# Diplomski.net
KiCad netlist of a schematic drawn in EasyEDA
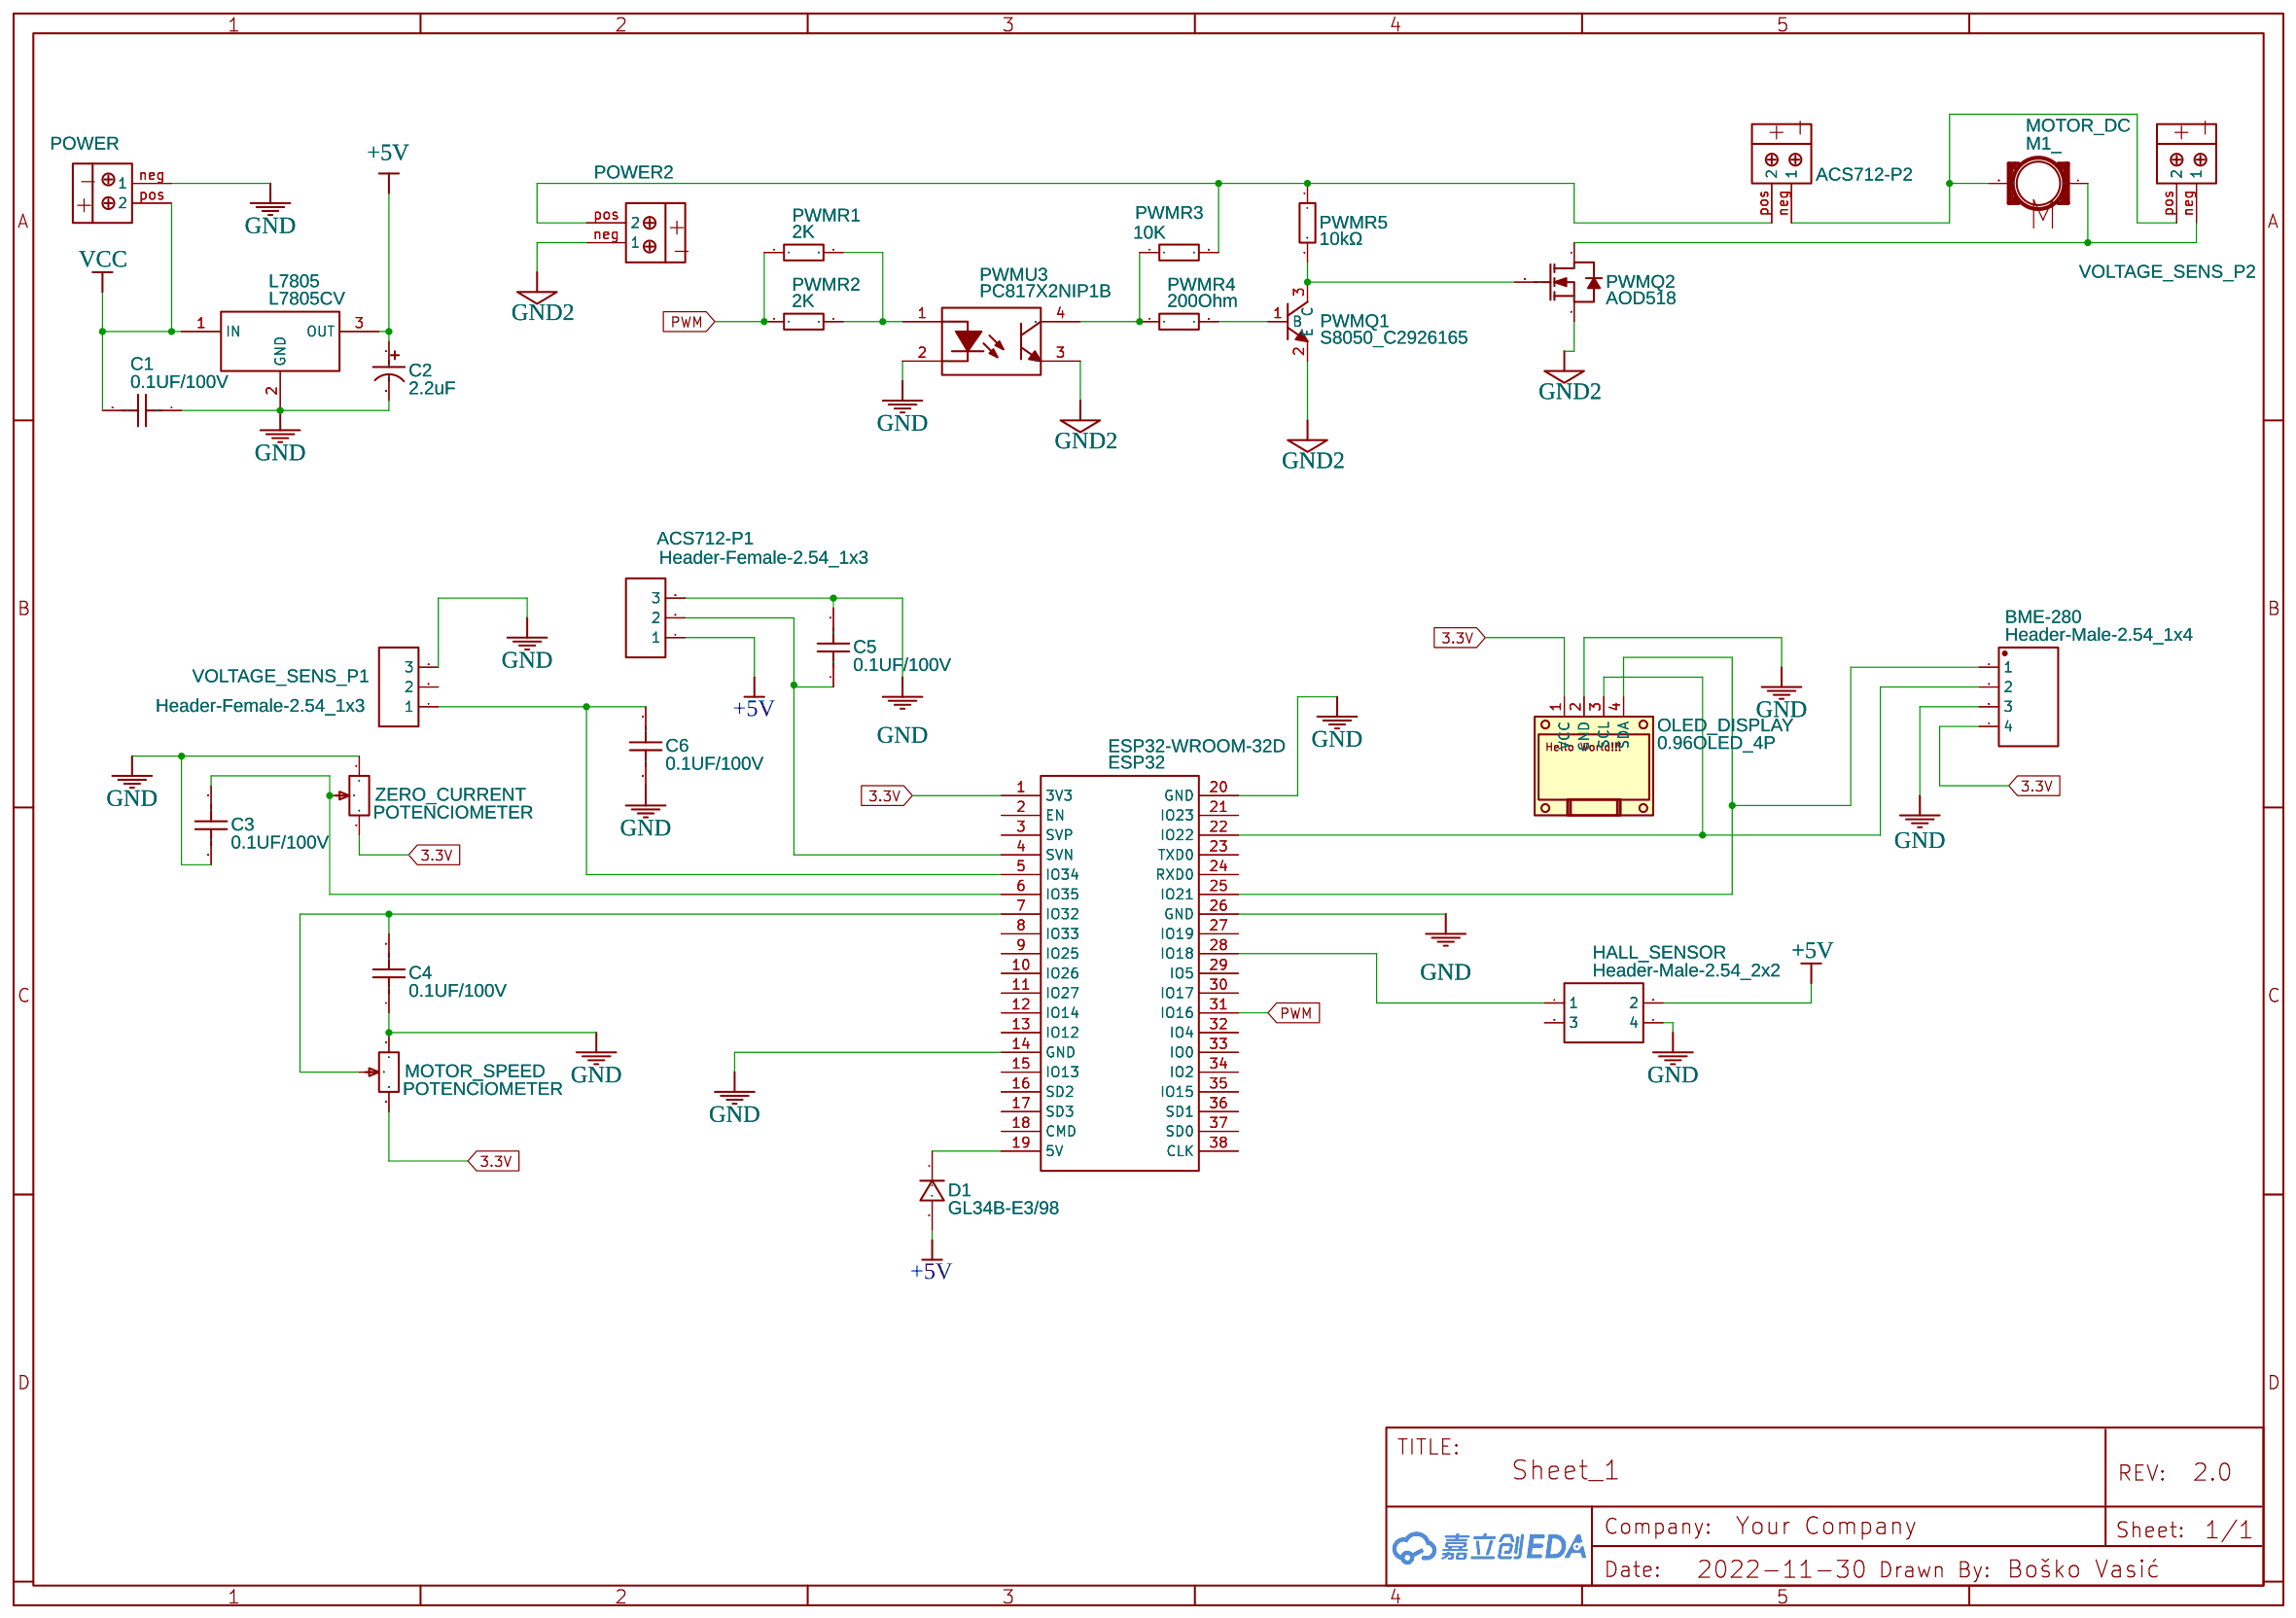
[diagram p0: schematic sheet]

(export (version "E")
  (design (tool "Eeschema 10.0.6"))
  (components
    (comp (ref "ACS712-P1")
      (value "Header-Female-2.54_1x3")
      (fields (field (name "BOM_Supplier Part") "C146243"))
      (libsource (lib "") (part "Header-Female-2.54_1x3_1"))
    )
    (comp (ref "ACS712-P2")
      (value "1X2 POWER PCB CONNECTO COPY")
      (fields (field (name "BOM_Manufacturer Part") "1x2 pin header"))
      (libsource (lib "") (part "1X2 POWER PCB CONNECTO COPY_2"))
    )
    (comp (ref "BME-280")
      (value "Header-Male-2.54_1x4")
      (fields
        (field (name "BOM_Manufacturer Part") "B-2100S04P-A110")
        (field (name "BOM_Supplier Part") "C124378")
      )
      (libsource (lib "") (part "Header-Male-2.54_1x4"))
    )
    (comp (ref "C1")
      (value "0.1UF/100V")
      (fields
        (field (name "BOM_Manufacturer Part") "0.1uF/100V")
        (field (name "BOM_Supplier Part") "C9900010259")
      )
      (libsource (lib "") (part "0.1UF/100V_1"))
    )
    (comp (ref "C2")
      (value "2.2uF")
      (fields
        (field (name "BOM_Manufacturer Part") "ERM1HM2R2D11OT")
        (field (name "BOM_Supplier Part") "C106603")
      )
      (libsource (lib "") (part "2.2UF 50V"))
    )
    (comp (ref "C3")
      (value "0.1UF/100V")
      (fields
        (field (name "BOM_Manufacturer Part") "0.1uF/100V")
        (field (name "BOM_Supplier Part") "C9900010259")
      )
      (libsource (lib "") (part "0.1UF/100V"))
    )
    (comp (ref "C4")
      (value "0.1UF/100V")
      (fields
        (field (name "BOM_Manufacturer Part") "0.1uF/100V")
        (field (name "BOM_Supplier Part") "C9900010259")
      )
      (libsource (lib "") (part "0.1UF/100V"))
    )
    (comp (ref "C5")
      (value "0.1UF/100V")
      (fields
        (field (name "BOM_Manufacturer Part") "0.1uF/100V")
        (field (name "BOM_Supplier Part") "C9900010259")
      )
      (libsource (lib "") (part "0.1UF/100V"))
    )
    (comp (ref "C6")
      (value "0.1UF/100V")
      (fields
        (field (name "BOM_Manufacturer Part") "0.1uF/100V")
        (field (name "BOM_Supplier Part") "C9900010259")
      )
      (libsource (lib "") (part "0.1UF/100V"))
    )
    (comp (ref "D1")
      (value "GL34B-E3/98")
      (fields (field (name "BOM_Supplier Part") "C222497"))
      (libsource (lib "") (part "GL34B-E3/98"))
    )
    (comp (ref "ESP32-WROOM-32D")
      (value "ESP32")
      (fields (field (name "BOM_Manufacturer Part") "ESP32-DEVKITC-32D"))
      (libsource (lib "") (part "Boiler"))
    )
    (comp (ref "HALL_SENSOR")
      (value "Header-Male-2.54_2x2")
      (fields
        (field (name "BOM_Manufacturer Part") "Double Rows2.54mm2*2pHeaders  Pins")
        (field (name "BOM_Supplier Part") "C66690")
      )
      (libsource (lib "") (part "Header-Male-2.54_2x2"))
    )
    (comp (ref "L7805")
      (value "L7805CV")
      (fields (field (name "BOM_Supplier Part") "C111887"))
      (libsource (lib "") (part "L7805CV"))
    )
    (comp (ref "MOTOR_DC") (value "M1_") (libsource (lib "") (part "Motor_DC")))
    (comp (ref "MOTOR_SPEED")
      (value "POTENCIOMETER")
      (fields (field (name "BOM_Manufacturer Part") "APAE_B10K_Potentiometer_Vertical"))
      (libsource (lib "") (part "POTENCIOMETER"))
    )
    (comp (ref "OLED_DISPLAY") (value "0.96OLED_4P") (libsource (lib "") (part "0.96OLED_4P")))
    (comp (ref "POWER")
      (value "1X2 POWER PCB CONNECTO COPY")
      (fields (field (name "BOM_Manufacturer Part") "1x2 pin header"))
      (libsource (lib "") (part "1X2 POWER PCB CONNECTO COPY"))
    )
    (comp (ref "POWER2")
      (value "POWER PCB CONNECTO 2")
      (fields (field (name "BOM_Manufacturer Part") "1x2 pin header"))
      (libsource (lib "") (part "1X2 POWER PCB CONNECTO COPY_3"))
    )
    (comp (ref "PWMQ1")
      (value "S8050_C2926165")
      (fields
        (field (name "BOM_Manufacturer Part") "S8050LT1 J3Y")
        (field (name "BOM_Supplier Part") "C2926165")
      )
      (libsource (lib "") (part "S8050_C2926165"))
    )
    (comp (ref "PWMQ2")
      (value "AOD518")
      (fields (field (name "BOM_Supplier Part") "C878924"))
      (libsource (lib "") (part "AOD518"))
    )
    (comp (ref "PWMR1")
      (value "2K")
      (fields
        (field (name "BOM_Manufacturer Part") "RC1206FR-070RL")
        (field (name "BOM_Supplier Part") "C137394")
      )
      (libsource (lib "") (part "RC1206FR-070RL"))
    )
    (comp (ref "PWMR2")
      (value "2K")
      (fields
        (field (name "BOM_Manufacturer Part") "RC1206FR-070RL")
        (field (name "BOM_Supplier Part") "C137394")
      )
      (libsource (lib "") (part "RC1206FR-070RL"))
    )
    (comp (ref "PWMR3")
      (value "10K")
      (fields
        (field (name "BOM_Manufacturer Part") "AC0805FR-0710KL")
        (field (name "BOM_Supplier Part") "C140868")
      )
      (libsource (lib "") (part "AC0805FR-0710KL"))
    )
    (comp (ref "PWMR4")
      (value "200Ohm")
      (fields
        (field (name "BOM_Manufacturer Part") "AC0805FR-0710KL")
        (field (name "BOM_Supplier Part") "C140868")
      )
      (libsource (lib "") (part "AC0805FR-0710KL"))
    )
    (comp (ref "PWMR5")
      (value "10kΩ")
      (fields
        (field (name "BOM_Manufacturer Part") "ARG05FTC2000")
        (field (name "BOM_Supplier Part") "C218416")
      )
      (libsource (lib "") (part "ARG05FTC2000"))
    )
    (comp (ref "PWMU3")
      (value "PC817X2NIP1B")
      (fields (field (name "BOM_Supplier Part") "C164149"))
      (libsource (lib "") (part "PC817X2NIP1B"))
    )
    (comp (ref "VOLTAGE_SENS_P1")
      (value "Header-Female-2.54_1x3")
      (fields (field (name "BOM_Supplier Part") "C146243"))
      (libsource (lib "") (part "Header-Female-2.54_1x3"))
    )
    (comp (ref "VOLTAGE_SENS_P2")
      (value "1X2 POWER PCB CONNECTO COPY")
      (fields (field (name "BOM_Manufacturer Part") "1x2 pin header"))
      (libsource (lib "") (part "1X2 POWER PCB CONNECTO COPY_1"))
    )
    (comp (ref "ZERO_CURRENT")
      (value "POTENCIOMETER")
      (fields (field (name "BOM_Manufacturer Part") "APAE_B10K_Potentiometer_Vertical"))
      (libsource (lib "") (part "POTENCIOMETER_1"))
    )
  )
  (nets
    (net (code "1") (name "+5V") (class "Default")
      (node (ref "ACS712-P1") (pin "1") (pinfunction "1_1") (pintype "input"))
      (node (ref "C2") (pin "1") (pinfunction "1_1") (pintype "input"))
      (node (ref "D1") (pin "2") (pinfunction "2_2") (pintype "unspecified"))
      (node (ref "HALL_SENSOR") (pin "2") (pinfunction "2_2") (pintype "input"))
      (node (ref "L7805") (pin "3") (pinfunction "OUT_3") (pintype "passive"))
    )
    (net (code "2") (name "3.3V") (class "Default")
      (node (ref "BME-280") (pin "4") (pinfunction "4_4") (pintype "unspecified"))
      (node (ref "ESP32-WROOM-32D") (pin "1") (pinfunction "3V3_1") (pintype "unspecified"))
      (node (ref "MOTOR_SPEED") (pin "3") (pinfunction "3_3") (pintype "input"))
      (node (ref "OLED_DISPLAY") (pin "1") (pinfunction "VCC_1") (pintype "unspecified"))
      (node (ref "ZERO_CURRENT") (pin "3") (pinfunction "3_3") (pintype "input"))
    )
    (net (code "3") (name "GND") (class "Default")
      (node (ref "ACS712-P1") (pin "3") (pinfunction "3_3") (pintype "input"))
      (node (ref "BME-280") (pin "3") (pinfunction "3_3") (pintype "unspecified"))
      (node (ref "C1") (pin "1") (pinfunction "1_1") (pintype "unspecified"))
      (node (ref "C2") (pin "2") (pinfunction "2_2") (pintype "input"))
      (node (ref "C3") (pin "1") (pinfunction "1_1") (pintype "unspecified"))
      (node (ref "C4") (pin "1") (pinfunction "1_1") (pintype "unspecified"))
      (node (ref "C5") (pin "2") (pinfunction "2_2") (pintype "unspecified"))
      (node (ref "C6") (pin "1") (pinfunction "1_1") (pintype "unspecified"))
      (node (ref "ESP32-WROOM-32D") (pin "14") (pinfunction "GND_14") (pintype "unspecified"))
      (node (ref "ESP32-WROOM-32D") (pin "20") (pinfunction "GND_20") (pintype "unspecified"))
      (node (ref "ESP32-WROOM-32D") (pin "26") (pinfunction "GND_26") (pintype "unspecified"))
      (node (ref "HALL_SENSOR") (pin "4") (pinfunction "4_4") (pintype "input"))
      (node (ref "L7805") (pin "2") (pinfunction "GND_2") (pintype "passive"))
      (node (ref "MOTOR_SPEED") (pin "1") (pinfunction "1_1") (pintype "input"))
      (node (ref "OLED_DISPLAY") (pin "2") (pinfunction "GND_2") (pintype "unspecified"))
      (node (ref "POWER") (pin "neg") (pinfunction "1_neg") (pintype "unspecified"))
      (node (ref "PWMU3") (pin "2") (pinfunction "CA_2") (pintype "unspecified"))
      (node (ref "VOLTAGE_SENS_P1") (pin "3") (pinfunction "3_3") (pintype "input"))
      (node (ref "ZERO_CURRENT") (pin "1") (pinfunction "1_1") (pintype "input"))
    )
    (net (code "4") (name "GND2") (class "Default")
      (node (ref "POWER2") (pin "neg") (pinfunction "1_neg") (pintype "unspecified"))
      (node (ref "PWMQ1") (pin "2") (pinfunction "E_2") (pintype "input"))
      (node (ref "PWMQ2") (pin "3") (pinfunction "S_3") (pintype "unspecified"))
      (node (ref "PWMU3") (pin "3") (pinfunction "EM_3") (pintype "unspecified"))
    )
    (net (code "5") (name "Net-(ACS712-P2-1)") (class "Default")
      (node (ref "ACS712-P2") (pin "neg") (pinfunction "1_neg") (pintype "unspecified"))
      (node (ref "MOTOR_DC") (pin "2") (pinfunction "2_2") (pintype "unspecified"))
      (node (ref "VOLTAGE_SENS_P2") (pin "pos") (pinfunction "2_pos") (pintype "unspecified"))
    )
    (net (code "6") (name "Net-(ACS712-P2-2)") (class "Default")
      (node (ref "ACS712-P2") (pin "pos") (pinfunction "2_pos") (pintype "unspecified"))
      (node (ref "POWER2") (pin "pos") (pinfunction "2_pos") (pintype "unspecified"))
      (node (ref "PWMR3") (pin "2") (pinfunction "2_2") (pintype "input"))
      (node (ref "PWMR5") (pin "1") (pinfunction "1_1") (pintype "unspecified"))
    )
    (net (code "7") (name "Net-(ESP32-WROOM-32D-5V)") (class "Default")
      (node (ref "D1") (pin "1") (pinfunction "1_1") (pintype "unspecified"))
      (node (ref "ESP32-WROOM-32D") (pin "19") (pinfunction "5V_19") (pintype "unspecified"))
    )
    (net (code "8") (name "Net-(ESP32-WROOM-32D-IO18)") (class "Default")
      (node (ref "ESP32-WROOM-32D") (pin "28") (pinfunction "IO18_28") (pintype "unspecified"))
      (node (ref "HALL_SENSOR") (pin "1") (pinfunction "1_1") (pintype "input"))
    )
    (net (code "9") (name "Net-(ESP32-WROOM-32D-IO21)") (class "Default")
      (node (ref "BME-280") (pin "1") (pinfunction "1_1") (pintype "unspecified"))
      (node (ref "ESP32-WROOM-32D") (pin "25") (pinfunction "IO21_25") (pintype "unspecified"))
      (node (ref "OLED_DISPLAY") (pin "4") (pinfunction "SDA_4") (pintype "unspecified"))
    )
    (net (code "10") (name "Net-(ESP32-WROOM-32D-IO22)") (class "Default")
      (node (ref "BME-280") (pin "2") (pinfunction "2_2") (pintype "unspecified"))
      (node (ref "ESP32-WROOM-32D") (pin "22") (pinfunction "IO22_22") (pintype "unspecified"))
      (node (ref "OLED_DISPLAY") (pin "3") (pinfunction "SCL_3") (pintype "unspecified"))
    )
    (net (code "11") (name "Net-(ESP32-WROOM-32D-IO32)") (class "Default")
      (node (ref "C4") (pin "2") (pinfunction "2_2") (pintype "unspecified"))
      (node (ref "ESP32-WROOM-32D") (pin "7") (pinfunction "IO32_7") (pintype "unspecified"))
      (node (ref "MOTOR_SPEED") (pin "2") (pinfunction "2_2") (pintype "input"))
    )
    (net (code "12") (name "Net-(ESP32-WROOM-32D-IO34)") (class "Default")
      (node (ref "C6") (pin "2") (pinfunction "2_2") (pintype "unspecified"))
      (node (ref "ESP32-WROOM-32D") (pin "5") (pinfunction "IO34_5") (pintype "unspecified"))
      (node (ref "VOLTAGE_SENS_P1") (pin "1") (pinfunction "1_1") (pintype "input"))
    )
    (net (code "13") (name "Net-(ESP32-WROOM-32D-IO35)") (class "Default")
      (node (ref "C3") (pin "2") (pinfunction "2_2") (pintype "unspecified"))
      (node (ref "ESP32-WROOM-32D") (pin "6") (pinfunction "IO35_6") (pintype "unspecified"))
      (node (ref "ZERO_CURRENT") (pin "2") (pinfunction "2_2") (pintype "input"))
    )
    (net (code "14") (name "Net-(ESP32-WROOM-32D-SVN)") (class "Default")
      (node (ref "ACS712-P1") (pin "2") (pinfunction "2_2") (pintype "input"))
      (node (ref "C5") (pin "1") (pinfunction "1_1") (pintype "unspecified"))
      (node (ref "ESP32-WROOM-32D") (pin "4") (pinfunction "SVN_4") (pintype "unspecified"))
    )
    (net (code "15") (name "Net-(PWMQ1-B)") (class "Default")
      (node (ref "PWMQ1") (pin "1") (pinfunction "B_1") (pintype "input"))
      (node (ref "PWMR4") (pin "2") (pinfunction "2_2") (pintype "input"))
    )
    (net (code "16") (name "Net-(PWMQ1-C)") (class "Default")
      (node (ref "PWMQ1") (pin "3") (pinfunction "C_3") (pintype "input"))
      (node (ref "PWMQ2") (pin "1") (pinfunction "G_1") (pintype "unspecified"))
      (node (ref "PWMR5") (pin "2") (pinfunction "2_2") (pintype "unspecified"))
    )
    (net (code "17") (name "Net-(PWMQ2-D)") (class "Default")
      (node (ref "MOTOR_DC") (pin "1") (pinfunction "1_1") (pintype "unspecified"))
      (node (ref "PWMQ2") (pin "2") (pinfunction "D_2") (pintype "unspecified"))
      (node (ref "VOLTAGE_SENS_P2") (pin "neg") (pinfunction "1_neg") (pintype "unspecified"))
    )
    (net (code "18") (name "Net-(PWMU3-AN)") (class "Default")
      (node (ref "PWMR1") (pin "2") (pinfunction "2_2") (pintype "input"))
      (node (ref "PWMR2") (pin "2") (pinfunction "2_2") (pintype "input"))
      (node (ref "PWMU3") (pin "1") (pinfunction "AN_1") (pintype "unspecified"))
    )
    (net (code "19") (name "Net-(PWMU3-COL)") (class "Default")
      (node (ref "PWMR3") (pin "1") (pinfunction "1_1") (pintype "input"))
      (node (ref "PWMR4") (pin "1") (pinfunction "1_1") (pintype "input"))
      (node (ref "PWMU3") (pin "4") (pinfunction "COL_4") (pintype "unspecified"))
    )
    (net (code "20") (name "PWM") (class "Default")
      (node (ref "ESP32-WROOM-32D") (pin "31") (pinfunction "IO16_31") (pintype "unspecified"))
      (node (ref "PWMR1") (pin "1") (pinfunction "1_1") (pintype "input"))
      (node (ref "PWMR2") (pin "1") (pinfunction "1_1") (pintype "input"))
    )
    (net (code "21") (name "VCC") (class "Default")
      (node (ref "C1") (pin "2") (pinfunction "2_2") (pintype "unspecified"))
      (node (ref "L7805") (pin "1") (pinfunction "IN_1") (pintype "passive"))
      (node (ref "POWER") (pin "pos") (pinfunction "2_pos") (pintype "unspecified"))
    )
    (net (code "22") (name "unconnected-(ESP32-WROOM-32D-CLK-Pad38)") (class "Default")
      (node (ref "ESP32-WROOM-32D") (pin "38") (pinfunction "CLK_38") (pintype "unspecified"))
    )
    (net (code "23") (name "unconnected-(ESP32-WROOM-32D-CMD-Pad18)") (class "Default")
      (node (ref "ESP32-WROOM-32D") (pin "18") (pinfunction "CMD_18") (pintype "unspecified"))
    )
    (net (code "24") (name "unconnected-(ESP32-WROOM-32D-EN-Pad2)") (class "Default")
      (node (ref "ESP32-WROOM-32D") (pin "2") (pinfunction "EN_2") (pintype "unspecified"))
    )
    (net (code "25") (name "unconnected-(ESP32-WROOM-32D-IO0-Pad33)") (class "Default")
      (node (ref "ESP32-WROOM-32D") (pin "33") (pinfunction "IO0_33") (pintype "unspecified"))
    )
    (net (code "26") (name "unconnected-(ESP32-WROOM-32D-IO2-Pad34)") (class "Default")
      (node (ref "ESP32-WROOM-32D") (pin "34") (pinfunction "IO2_34") (pintype "unspecified"))
    )
    (net (code "27") (name "unconnected-(ESP32-WROOM-32D-IO4-Pad32)") (class "Default")
      (node (ref "ESP32-WROOM-32D") (pin "32") (pinfunction "IO4_32") (pintype "unspecified"))
    )
    (net (code "28") (name "unconnected-(ESP32-WROOM-32D-IO5-Pad29)") (class "Default")
      (node (ref "ESP32-WROOM-32D") (pin "29") (pinfunction "IO5_29") (pintype "unspecified"))
    )
    (net (code "29") (name "unconnected-(ESP32-WROOM-32D-IO12-Pad13)") (class "Default")
      (node (ref "ESP32-WROOM-32D") (pin "13") (pinfunction "IO12_13") (pintype "unspecified"))
    )
    (net (code "30") (name "unconnected-(ESP32-WROOM-32D-IO13-Pad15)") (class "Default")
      (node (ref "ESP32-WROOM-32D") (pin "15") (pinfunction "IO13_15") (pintype "unspecified"))
    )
    (net (code "31") (name "unconnected-(ESP32-WROOM-32D-IO14-Pad12)") (class "Default")
      (node (ref "ESP32-WROOM-32D") (pin "12") (pinfunction "IO14_12") (pintype "unspecified"))
    )
    (net (code "32") (name "unconnected-(ESP32-WROOM-32D-IO15-Pad35)") (class "Default")
      (node (ref "ESP32-WROOM-32D") (pin "35") (pinfunction "IO15_35") (pintype "unspecified"))
    )
    (net (code "33") (name "unconnected-(ESP32-WROOM-32D-IO17-Pad30)") (class "Default")
      (node (ref "ESP32-WROOM-32D") (pin "30") (pinfunction "IO17_30") (pintype "unspecified"))
    )
    (net (code "34") (name "unconnected-(ESP32-WROOM-32D-IO19-Pad27)") (class "Default")
      (node (ref "ESP32-WROOM-32D") (pin "27") (pinfunction "IO19_27") (pintype "unspecified"))
    )
    (net (code "35") (name "unconnected-(ESP32-WROOM-32D-IO23-Pad21)") (class "Default")
      (node (ref "ESP32-WROOM-32D") (pin "21") (pinfunction "IO23_21") (pintype "unspecified"))
    )
    (net (code "36") (name "unconnected-(ESP32-WROOM-32D-IO25-Pad9)") (class "Default")
      (node (ref "ESP32-WROOM-32D") (pin "9") (pinfunction "IO25_9") (pintype "unspecified"))
    )
    (net (code "37") (name "unconnected-(ESP32-WROOM-32D-IO26-Pad10)") (class "Default")
      (node (ref "ESP32-WROOM-32D") (pin "10") (pinfunction "IO26_10") (pintype "unspecified"))
    )
    (net (code "38") (name "unconnected-(ESP32-WROOM-32D-IO27-Pad11)") (class "Default")
      (node (ref "ESP32-WROOM-32D") (pin "11") (pinfunction "IO27_11") (pintype "unspecified"))
    )
    (net (code "39") (name "unconnected-(ESP32-WROOM-32D-IO33-Pad8)") (class "Default")
      (node (ref "ESP32-WROOM-32D") (pin "8") (pinfunction "IO33_8") (pintype "unspecified"))
    )
    (net (code "40") (name "unconnected-(ESP32-WROOM-32D-RXD0-Pad24)") (class "Default")
      (node (ref "ESP32-WROOM-32D") (pin "24") (pinfunction "RXD0_24") (pintype "unspecified"))
    )
    (net (code "41") (name "unconnected-(ESP32-WROOM-32D-SD0-Pad37)") (class "Default")
      (node (ref "ESP32-WROOM-32D") (pin "37") (pinfunction "SD0_37") (pintype "unspecified"))
    )
    (net (code "42") (name "unconnected-(ESP32-WROOM-32D-SD1-Pad36)") (class "Default")
      (node (ref "ESP32-WROOM-32D") (pin "36") (pinfunction "SD1_36") (pintype "unspecified"))
    )
    (net (code "43") (name "unconnected-(ESP32-WROOM-32D-SD2-Pad16)") (class "Default")
      (node (ref "ESP32-WROOM-32D") (pin "16") (pinfunction "SD2_16") (pintype "unspecified"))
    )
    (net (code "44") (name "unconnected-(ESP32-WROOM-32D-SD3-Pad17)") (class "Default")
      (node (ref "ESP32-WROOM-32D") (pin "17") (pinfunction "SD3_17") (pintype "unspecified"))
    )
    (net (code "45") (name "unconnected-(ESP32-WROOM-32D-SVP-Pad3)") (class "Default")
      (node (ref "ESP32-WROOM-32D") (pin "3") (pinfunction "SVP_3") (pintype "unspecified"))
    )
    (net (code "46") (name "unconnected-(ESP32-WROOM-32D-TXD0-Pad23)") (class "Default")
      (node (ref "ESP32-WROOM-32D") (pin "23") (pinfunction "TXD0_23") (pintype "unspecified"))
    )
    (net (code "47") (name "unconnected-(HALL_SENSOR-Pad3)") (class "Default")
      (node (ref "HALL_SENSOR") (pin "3") (pinfunction "3_3") (pintype "input"))
    )
    (net (code "48") (name "unconnected-(VOLTAGE_SENS_P1-Pad2)") (class "Default")
      (node (ref "VOLTAGE_SENS_P1") (pin "2") (pinfunction "2_2") (pintype "input"))
    )
  )
)
